# ABL_RP2040.net
KiCad netlist of a schematic drawn in EAGLE
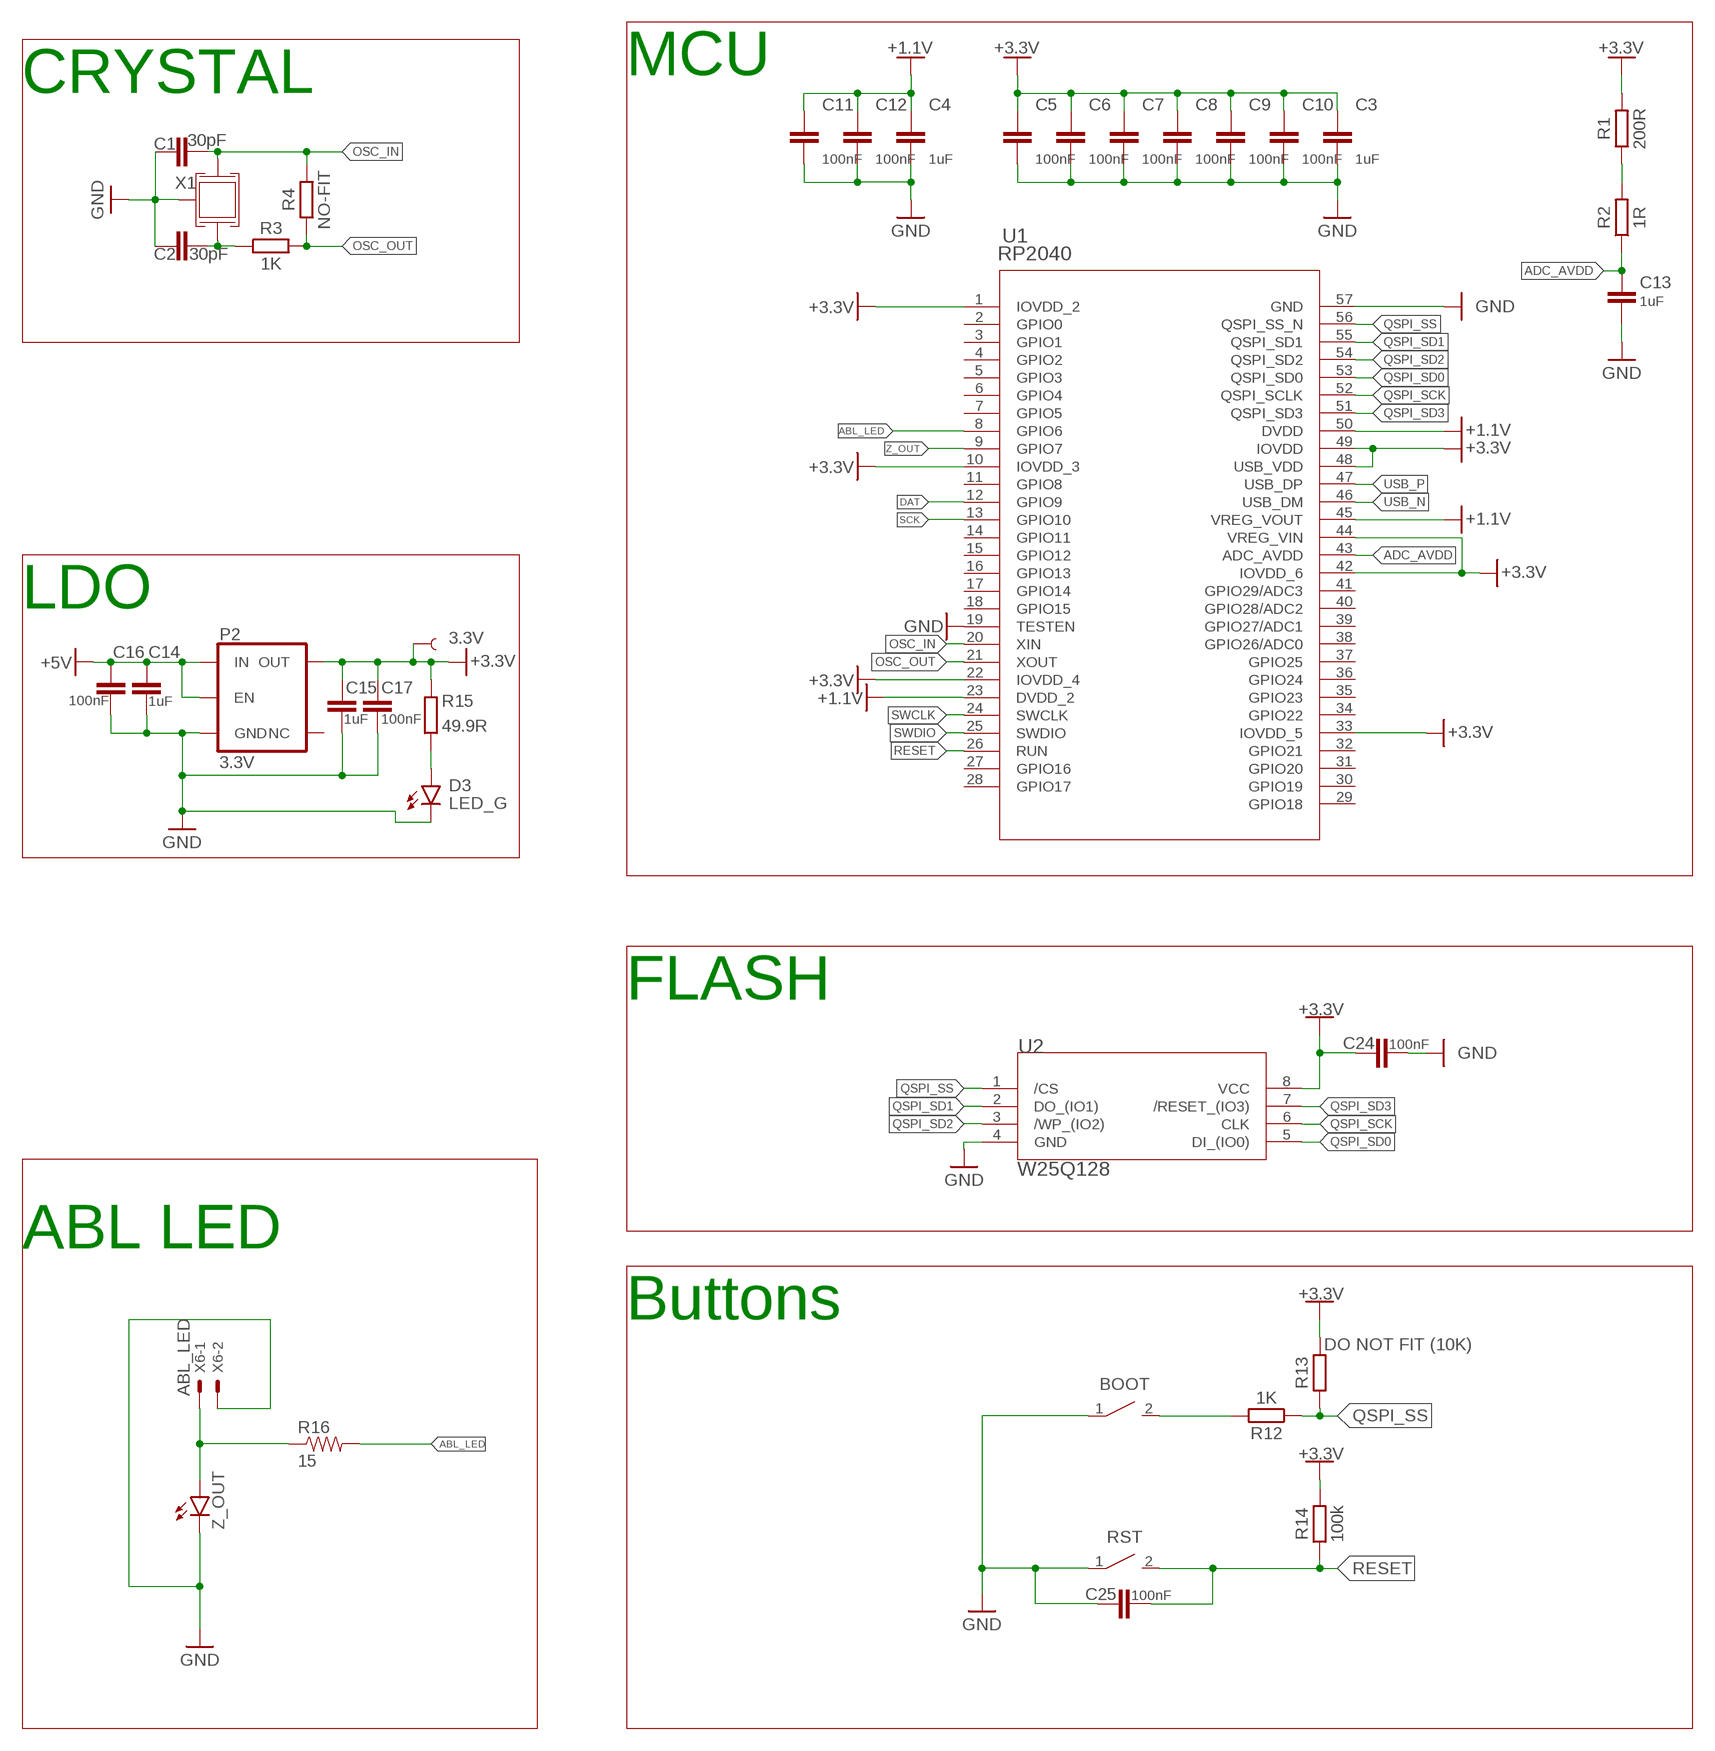
[diagram p0: schematic, sheet 1, part 1 of 2]
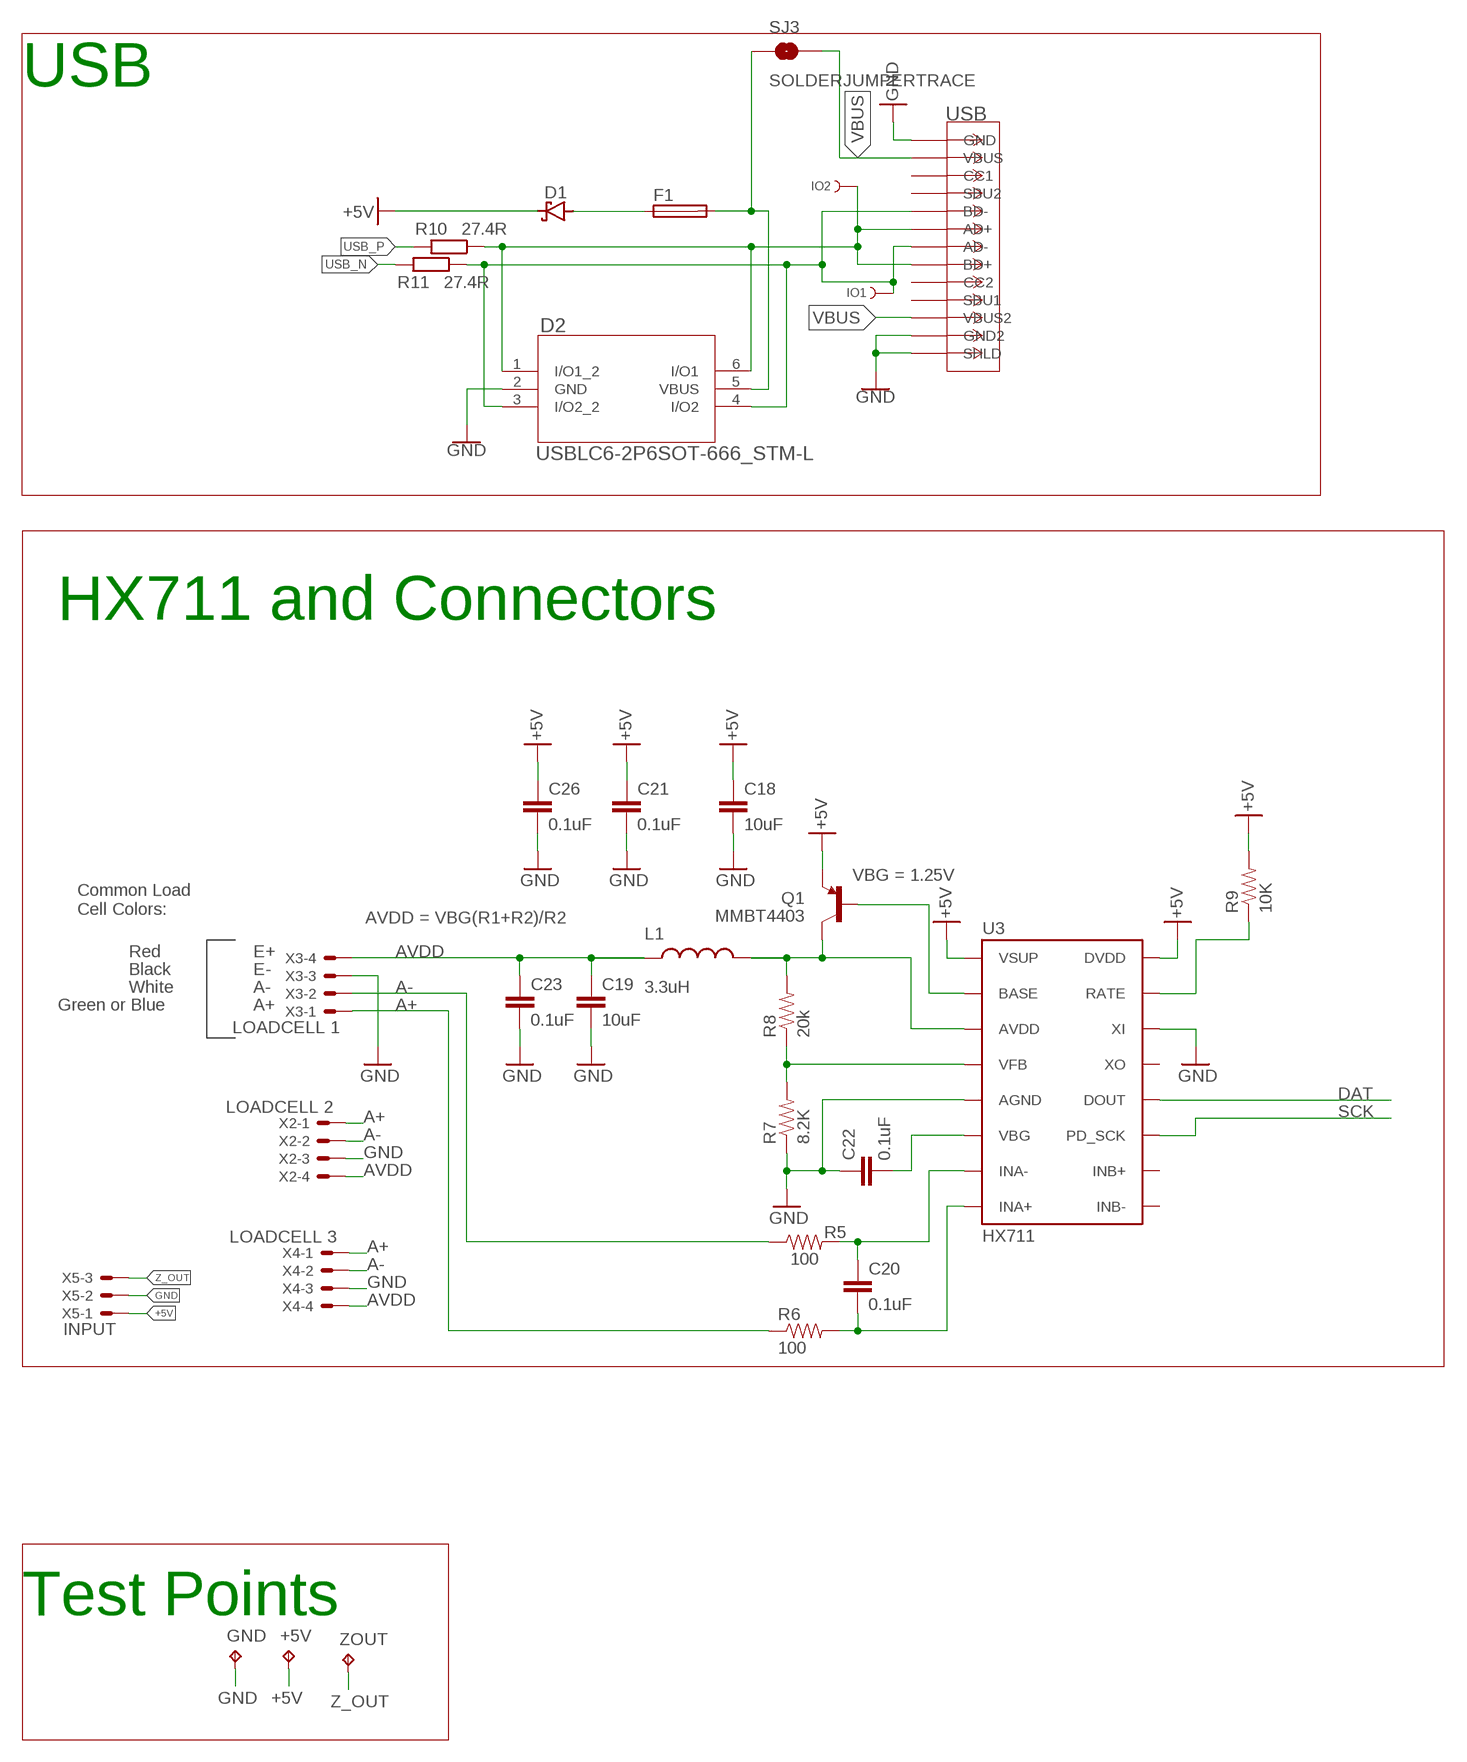
[diagram p1: schematic, sheet 1, part 2 of 2]

(export (version "E")
  (design (tool "Eeschema 10.0.6"))
  (components
    (comp (ref "+5V")
      (value "TPB2,54")
      (footprint "eagle-import:B2,54")
      (libsource (lib "eagle-import") (part "TPB2,54"))
    )
    (comp (ref "3.3V")
      (value "TEST-POINT3X4")
      (footprint "eagle-import:PAD.03X.04")
      (libsource (lib "eagle-import") (part "TEST-POINT3X4"))
    )
    (comp (ref "BOOT")
      (value "B3U-1000P(M)-B")
      (footprint "eagle-import:B3U-1000P(M)-B")
      (fields (field (name "MANUFACTURER") "OMRON"))
      (libsource (lib "eagle-import") (part "B3U-X0001000P(M)-BB3U-1000P(M)-B"))
    )
    (comp (ref "C1")
      (value "30pF")
      (footprint "eagle-import:CAPC1005X60")
      (libsource (lib "eagle-import") (part "CCHIP-0402(1005-METRIC)_"))
    )
    (comp (ref "C2")
      (value "30pF")
      (footprint "eagle-import:CAPC1005X60")
      (libsource (lib "eagle-import") (part "CCHIP-0402(1005-METRIC)_"))
    )
    (comp (ref "C3")
      (value "1uF")
      (footprint "eagle-import:CAPC1005X60")
      (libsource (lib "eagle-import") (part "CCHIP-0402(1005-METRIC)_"))
    )
    (comp (ref "C4")
      (value "1uF")
      (footprint "eagle-import:CAPC1005X60")
      (libsource (lib "eagle-import") (part "CCHIP-0402(1005-METRIC)_"))
    )
    (comp (ref "C5")
      (value "100nF")
      (footprint "eagle-import:CAPC1005X60")
      (libsource (lib "eagle-import") (part "CCHIP-0402(1005-METRIC)_"))
    )
    (comp (ref "C6")
      (value "100nF")
      (footprint "eagle-import:CAPC1005X60")
      (libsource (lib "eagle-import") (part "CCHIP-0402(1005-METRIC)_"))
    )
    (comp (ref "C7")
      (value "100nF")
      (footprint "eagle-import:CAPC1005X60")
      (libsource (lib "eagle-import") (part "CCHIP-0402(1005-METRIC)_"))
    )
    (comp (ref "C8")
      (value "100nF")
      (footprint "eagle-import:CAPC1005X60")
      (libsource (lib "eagle-import") (part "CCHIP-0402(1005-METRIC)_"))
    )
    (comp (ref "C9")
      (value "100nF")
      (footprint "eagle-import:CAPC1005X60")
      (libsource (lib "eagle-import") (part "CCHIP-0402(1005-METRIC)_"))
    )
    (comp (ref "C10")
      (value "100nF")
      (footprint "eagle-import:CAPC1005X60")
      (libsource (lib "eagle-import") (part "CCHIP-0402(1005-METRIC)_"))
    )
    (comp (ref "C11")
      (value "100nF")
      (footprint "eagle-import:CAPC1005X60")
      (libsource (lib "eagle-import") (part "CCHIP-0402(1005-METRIC)_"))
    )
    (comp (ref "C12")
      (value "100nF")
      (footprint "eagle-import:CAPC1005X60")
      (libsource (lib "eagle-import") (part "CCHIP-0402(1005-METRIC)_"))
    )
    (comp (ref "C13")
      (value "1uF")
      (footprint "eagle-import:CAPC1005X60")
      (libsource (lib "eagle-import") (part "CCHIP-0402(1005-METRIC)_"))
    )
    (comp (ref "C14")
      (value "1uF")
      (footprint "eagle-import:CAPC1005X60")
      (libsource (lib "eagle-import") (part "CCHIP-0402(1005-METRIC)_"))
    )
    (comp (ref "C15")
      (value "1uF")
      (footprint "eagle-import:CAPC1005X60")
      (libsource (lib "eagle-import") (part "CCHIP-0402(1005-METRIC)_"))
    )
    (comp (ref "C16")
      (value "100nF")
      (footprint "eagle-import:CAPC1005X60")
      (libsource (lib "eagle-import") (part "CCHIP-0402(1005-METRIC)_"))
    )
    (comp (ref "C17")
      (value "100nF")
      (footprint "eagle-import:CAPC1005X60")
      (libsource (lib "eagle-import") (part "CCHIP-0402(1005-METRIC)_"))
    )
    (comp (ref "C18")
      (value "10uF")
      (footprint "eagle-import:1210")
      (libsource (lib "eagle-import") (part "10UF50V20%(1210)"))
    )
    (comp (ref "C19")
      (value "10uF")
      (footprint "eagle-import:1210")
      (libsource (lib "eagle-import") (part "10UF50V20%(1210)"))
    )
    (comp (ref "C20")
      (value "0.1uF")
      (footprint "eagle-import:0603-CAP")
      (libsource (lib "eagle-import") (part "0.1UF-25V-5%(0603)"))
    )
    (comp (ref "C21")
      (value "0.1uF")
      (footprint "eagle-import:0603-CAP")
      (libsource (lib "eagle-import") (part "0.1UF-25V-5%(0603)"))
    )
    (comp (ref "C22")
      (value "0.1uF")
      (footprint "eagle-import:0603-CAP")
      (libsource (lib "eagle-import") (part "0.1UF-25V-5%(0603)"))
    )
    (comp (ref "C23")
      (value "0.1uF")
      (footprint "eagle-import:0603-CAP")
      (libsource (lib "eagle-import") (part "0.1UF-25V-5%(0603)"))
    )
    (comp (ref "C24")
      (value "100nF")
      (footprint "eagle-import:CAPC1005X60")
      (libsource (lib "eagle-import") (part "CCHIP-0402(1005-METRIC)_"))
    )
    (comp (ref "C25")
      (value "100nF")
      (footprint "eagle-import:CAPC1005X60")
      (libsource (lib "eagle-import") (part "CCHIP-0402(1005-METRIC)_"))
    )
    (comp (ref "C26")
      (value "0.1uF")
      (footprint "eagle-import:0603-CAP")
      (libsource (lib "eagle-import") (part "0.1UF-25V-5%(0603)"))
    )
    (comp (ref "D1")
      (value "MBR0520LT1G")
      (footprint "eagle-import:SODFL3718X115")
      (fields (field (name "MANUFACTURER") "ON Semiconductor"))
      (libsource (lib "eagle-import") (part "SCHOTTKY_DO-219MBR0520LT1G"))
    )
    (comp (ref "D2")
      (value "USBLC6-2P6SOT-666_STM-L")
      (footprint "eagle-import:SOT-666_STM-L")
      (fields
        (field (name "MANUFACTURER_PART_NUMBER") "USBLC6-2P6")
        (field (name "COPYRIGHT") "Copyright (C) 2023 Ultra Librarian. All rights reserved.")
      )
      (libsource (lib "eagle-import") (part "USBLC6-2P6SOT-666_STM-L"))
    )
    (comp (ref "D3")
      (value "LED_G")
      (footprint "eagle-import:LEDC1608X35N_FLAT-G")
      (libsource (lib "eagle-import") (part "CHIP-FLAT-G_0603-0.35MM"))
    )
    (comp (ref "F1")
      (value "FUSE_CHIP-0603(1608-METRIC)")
      (footprint "eagle-import:FUSC1608X60N")
      (libsource (lib "eagle-import") (part "FUSECHIP-0603(1608-METRIC)_"))
    )
    (comp (ref "GND")
      (value "TPB2,54")
      (footprint "eagle-import:B2,54")
      (libsource (lib "eagle-import") (part "TPB2,54"))
    )
    (comp (ref "IO1")
      (value "TEST-POINT3")
      (footprint "eagle-import:PAD.03X.03")
      (libsource (lib "eagle-import") (part "TEST-POINT3"))
    )
    (comp (ref "IO2")
      (value "TEST-POINT3")
      (footprint "eagle-import:PAD.03X.03")
      (libsource (lib "eagle-import") (part "TEST-POINT3"))
    )
    (comp (ref "L1")
      (value "3.3uH")
      (footprint "eagle-import:0805")
      (libsource (lib "eagle-import") (part "INDUCTOR0805-IND"))
    )
    (comp (ref "P2")
      (value "3.3V")
      (footprint "eagle-import:SOT23-5")
      (libsource (lib "eagle-import") (part "V_REG_AP2112K-3.3V"))
    )
    (comp (ref "Q1")
      (value "MMBT4403")
      (footprint "eagle-import:SOT23-3")
      (libsource (lib "eagle-import") (part "TRANSISTOR_PNPMMBT4403"))
    )
    (comp (ref "R1")
      (value "200R")
      (footprint "eagle-import:RESC1005X40")
      (libsource (lib "eagle-import") (part "RCHIP-0402(1005-METRIC)_"))
    )
    (comp (ref "R2")
      (value "1R")
      (footprint "eagle-import:RESC1005X40")
      (libsource (lib "eagle-import") (part "RCHIP-0402(1005-METRIC)_"))
    )
    (comp (ref "R3")
      (value "1K")
      (footprint "eagle-import:RESC1005X40")
      (libsource (lib "eagle-import") (part "RCHIP-0402(1005-METRIC)_"))
    )
    (comp (ref "R4")
      (value "NO-FIT")
      (footprint "eagle-import:RESC1005X40")
      (libsource (lib "eagle-import") (part "RCHIP-0402(1005-METRIC)_"))
    )
    (comp (ref "R5")
      (value "100")
      (footprint "eagle-import:0603-RES@1")
      (libsource (lib "eagle-import") (part "100OHM-1/10W-1%(0603)"))
    )
    (comp (ref "R6")
      (value "100")
      (footprint "eagle-import:0603-RES@1")
      (libsource (lib "eagle-import") (part "100OHM-1/10W-1%(0603)"))
    )
    (comp (ref "R7")
      (value "8.2K")
      (footprint "eagle-import:0603-RES")
      (libsource (lib "eagle-import") (part "8.2KOHM-1/10W-5%(0603)"))
    )
    (comp (ref "R8")
      (value "20k")
      (footprint "eagle-import:0603-RES")
      (libsource (lib "eagle-import") (part "20KOHM1/10W1%(0603)"))
    )
    (comp (ref "R9")
      (value "10K")
      (footprint "eagle-import:0603-RES@1")
      (libsource (lib "eagle-import") (part "10KOHM-1/10W-1%(0603)0603"))
    )
    (comp (ref "R10")
      (value "27.4R")
      (footprint "eagle-import:RESC1005X40")
      (libsource (lib "eagle-import") (part "RCHIP-0402(1005-METRIC)_"))
    )
    (comp (ref "R11")
      (value "27.4R")
      (footprint "eagle-import:RESC1005X40")
      (libsource (lib "eagle-import") (part "RCHIP-0402(1005-METRIC)_"))
    )
    (comp (ref "R12")
      (value "1K")
      (footprint "eagle-import:RESC1005X40")
      (libsource (lib "eagle-import") (part "RCHIP-0402(1005-METRIC)_"))
    )
    (comp (ref "R13")
      (value "DO NOT FIT (10K)")
      (footprint "eagle-import:RESC1005X40")
      (libsource (lib "eagle-import") (part "RCHIP-0402(1005-METRIC)_"))
    )
    (comp (ref "R14")
      (value "100k")
      (footprint "eagle-import:RESC1005X40")
      (libsource (lib "eagle-import") (part "RCHIP-0402(1005-METRIC)_"))
    )
    (comp (ref "R15")
      (value "49.9R")
      (footprint "eagle-import:RESC1005X40")
      (libsource (lib "eagle-import") (part "RCHIP-0402(1005-METRIC)_"))
    )
    (comp (ref "R16")
      (value "15")
      (footprint "eagle-import:0603-RES")
      (libsource (lib "eagle-import") (part "RESISTOR0603"))
    )
    (comp (ref "RST")
      (value "B3U-1000P(M)-B")
      (footprint "eagle-import:B3U-1000P(M)-B")
      (fields (field (name "MANUFACTURER") "OMRON"))
      (libsource (lib "eagle-import") (part "B3U-X0001000P(M)-BB3U-1000P(M)-B"))
    )
    (comp (ref "SJ3")
      (value "SOLDERJUMPERTRACE")
      (footprint "eagle-import:SJ_2S-TRACE")
      (libsource (lib "eagle-import") (part "SOLDERJUMPERTRACE"))
    )
    (comp (ref "U1")
      (value "RP2040")
      (footprint "eagle-import:IC57_RP2040-L")
      (fields (field (name "COPYRIGHT") "Copyright (C) 2023 Ultra Librarian. All rights reserved."))
      (libsource (lib "eagle-import") (part "RP2040IC57_RP2040-L"))
    )
    (comp (ref "U2")
      (value "W25Q128")
      (footprint "eagle-import:SOIC_128JVSIQ_WIN-L")
      (fields
        (field (name "MANUFACTURER_PART_NUMBER") "W25Q128JVSIQ")
        (field (name "COPYRIGHT") "Copyright (C) 2023 Ultra Librarian. All rights reserved.")
      )
      (libsource (lib "eagle-import") (part "W25Q128JVSIQSOIC_128JVSIQ_WIN-L"))
    )
    (comp (ref "U3")
      (value "HX711")
      (footprint "eagle-import:SO16")
      (libsource (lib "eagle-import") (part "HX711HX711"))
    )
    (comp (ref "USB")
      (value "USB-C(KH-TYPE-C-16P)")
      (footprint "eagle-import:CONN12_KH-TYPE-C-16P")
      (fields
        (field (name "MANUFACTURER_PART_NUMBER") "DX07S016JA1R1500")
        (field (name "VENDOR") "LCSC")
        (field (name "COPYRIGHT") "Copyright (C) 2018 Accelerated Designs. All rights reserved")
        (field (name "SOURCELIBRARY") "JAE_Electronics_2020-03-30")
      )
      (libsource (lib "eagle-import") (part "USB-C(KH-TYPE-C-16P)"))
    )
    (comp (ref "X1")
      (value "CRYSTAL_TAXM12M4RLBDDT2T_3225")
      (footprint "eagle-import:CRYSTAL_3225")
      (libsource (lib "eagle-import") (part "CRYSTAL_TAXM12M4RLBDDT2T_3225"))
    )
    (comp (ref "X2")
      (value "LOADCELL 2")
      (footprint "eagle-import:JST-XH-04-PACKAGE-LONG-PAD")
      (libsource (lib "eagle-import") (part "JST-XH-04-PIN-LONG-PAD"))
    )
    (comp (ref "X3")
      (value "LOADCELL 1")
      (footprint "eagle-import:JST-XH-04-PACKAGE-LONG-PAD")
      (libsource (lib "eagle-import") (part "JST-XH-04-PIN-LONG-PAD"))
    )
    (comp (ref "X4")
      (value "LOADCELL 3")
      (footprint "eagle-import:JST-XH-04-PACKAGE-LONG-PAD")
      (libsource (lib "eagle-import") (part "JST-XH-04-PIN-LONG-PAD"))
    )
    (comp (ref "X5")
      (value "INPUT")
      (footprint "eagle-import:JST-XH-03-PACKAGE-LONG-PAD")
      (libsource (lib "eagle-import") (part "JST-XH-03-PIN-LONG-PAD"))
    )
    (comp (ref "X6")
      (value "ABL_LED")
      (footprint "eagle-import:JST-XH-02-PACKAGE-LONG-PAD")
      (libsource (lib "eagle-import") (part "JST-XH-02-PIN-LONG-PAD"))
    )
    (comp (ref "ZOUT")
      (value "TPB2,54")
      (footprint "eagle-import:B2,54")
      (libsource (lib "eagle-import") (part "TPB2,54"))
    )
    (comp (ref "Z_OUT")
      (value "LEDSML0603")
      (footprint "eagle-import:SML0603")
      (libsource (lib "eagle-import") (part "LEDSML0603"))
    )
  )
  (nets
    (net (code "1") (name "+1.1V") (class "Default")
      (node (ref "C11") (pin "1") (pinfunction "1_1") (pintype "passive"))
      (node (ref "C12") (pin "1") (pinfunction "1_1") (pintype "passive"))
      (node (ref "C4") (pin "1") (pinfunction "1_1") (pintype "passive"))
      (node (ref "U1") (pin "23") (pinfunction "DVDD_2_23") (pintype "power_in"))
      (node (ref "U1") (pin "45") (pinfunction "VREG_VOUT_45") (pintype "output"))
      (node (ref "U1") (pin "50") (pinfunction "DVDD_50") (pintype "power_in"))
    )
    (net (code "2") (name "+3.3V") (class "Default")
      (node (ref "3.3V") (pin "P$1") (pinfunction "1_P$1") (pintype "bidirectional"))
      (node (ref "C10") (pin "1") (pinfunction "1_1") (pintype "passive"))
      (node (ref "C15") (pin "1") (pinfunction "1_1") (pintype "passive"))
      (node (ref "C17") (pin "1") (pinfunction "1_1") (pintype "passive"))
      (node (ref "C24") (pin "1") (pinfunction "1_1") (pintype "passive"))
      (node (ref "C3") (pin "1") (pinfunction "1_1") (pintype "passive"))
      (node (ref "C5") (pin "1") (pinfunction "1_1") (pintype "passive"))
      (node (ref "C6") (pin "1") (pinfunction "1_1") (pintype "passive"))
      (node (ref "C7") (pin "1") (pinfunction "1_1") (pintype "passive"))
      (node (ref "C8") (pin "1") (pinfunction "1_1") (pintype "passive"))
      (node (ref "C9") (pin "1") (pinfunction "1_1") (pintype "passive"))
      (node (ref "P2") (pin "5") (pinfunction "OUT_5") (pintype "passive"))
      (node (ref "R1") (pin "2") (pinfunction "2_2") (pintype "passive"))
      (node (ref "R13") (pin "2") (pinfunction "2_2") (pintype "passive"))
      (node (ref "R14") (pin "2") (pinfunction "2_2") (pintype "passive"))
      (node (ref "R15") (pin "2") (pinfunction "2_2") (pintype "passive"))
      (node (ref "U1") (pin "1") (pinfunction "IOVDD_2_1") (pintype "power_in"))
      (node (ref "U1") (pin "10") (pinfunction "IOVDD_3_10") (pintype "power_in"))
      (node (ref "U1") (pin "22") (pinfunction "IOVDD_4_22") (pintype "power_in"))
      (node (ref "U1") (pin "33") (pinfunction "IOVDD_5_33") (pintype "power_in"))
      (node (ref "U1") (pin "42") (pinfunction "IOVDD_6_42") (pintype "power_in"))
      (node (ref "U1") (pin "44") (pinfunction "VREG_VIN_44") (pintype "passive"))
      (node (ref "U1") (pin "48") (pinfunction "USB_VDD_48") (pintype "power_in"))
      (node (ref "U1") (pin "49") (pinfunction "IOVDD_49") (pintype "power_in"))
      (node (ref "U2") (pin "8") (pinfunction "VCC_8") (pintype "power_in"))
    )
    (net (code "3") (name "+5V") (class "Default")
      (node (ref "+5V") (pin "TP") (pinfunction "TP_TP") (pintype "input"))
      (node (ref "C14") (pin "1") (pinfunction "1_1") (pintype "passive"))
      (node (ref "C16") (pin "1") (pinfunction "1_1") (pintype "passive"))
      (node (ref "C18") (pin "1") (pinfunction "1_1") (pintype "passive"))
      (node (ref "C21") (pin "1") (pinfunction "1_1") (pintype "passive"))
      (node (ref "C26") (pin "1") (pinfunction "1_1") (pintype "passive"))
      (node (ref "D1") (pin "1") (pinfunction "C_1") (pintype "passive"))
      (node (ref "P2") (pin "1") (pinfunction "IN_1") (pintype "input"))
      (node (ref "P2") (pin "3") (pinfunction "EN_3") (pintype "input"))
      (node (ref "Q1") (pin "2") (pinfunction "E_2") (pintype "passive"))
      (node (ref "R9") (pin "2") (pinfunction "2_2") (pintype "passive"))
      (node (ref "U3") (pin "1") (pinfunction "VSUP_1") (pintype "bidirectional"))
      (node (ref "U3") (pin "16") (pinfunction "DVDD_16") (pintype "bidirectional"))
      (node (ref "X5") (pin "1") (pinfunction "S_1") (pintype "passive"))
    )
    (net (code "4") (name "/A+") (class "Default")
      (node (ref "R6") (pin "1") (pinfunction "1_1") (pintype "passive"))
      (node (ref "X2") (pin "1") (pinfunction "S_1") (pintype "passive"))
      (node (ref "X3") (pin "1") (pinfunction "S_1") (pintype "passive"))
      (node (ref "X4") (pin "1") (pinfunction "S_1") (pintype "passive"))
    )
    (net (code "5") (name "/A-") (class "Default")
      (node (ref "R5") (pin "1") (pinfunction "1_1") (pintype "passive"))
      (node (ref "X2") (pin "2") (pinfunction "S_2") (pintype "passive"))
      (node (ref "X3") (pin "2") (pinfunction "S_2") (pintype "passive"))
      (node (ref "X4") (pin "2") (pinfunction "S_2") (pintype "passive"))
    )
    (net (code "6") (name "/AVDD") (class "Default")
      (node (ref "C19") (pin "1") (pinfunction "1_1") (pintype "passive"))
      (node (ref "C23") (pin "1") (pinfunction "1_1") (pintype "passive"))
      (node (ref "L1") (pin "1") (pinfunction "1_1") (pintype "passive"))
      (node (ref "X2") (pin "4") (pinfunction "S_4") (pintype "passive"))
      (node (ref "X3") (pin "4") (pinfunction "S_4") (pintype "passive"))
      (node (ref "X4") (pin "4") (pinfunction "S_4") (pintype "passive"))
    )
    (net (code "7") (name "ABL_LED") (class "Default")
      (node (ref "R16") (pin "2") (pinfunction "2_2") (pintype "passive"))
      (node (ref "U1") (pin "8") (pinfunction "GPIO6_8") (pintype "bidirectional"))
    )
    (net (code "8") (name "ADC_AVDD") (class "Default")
      (node (ref "C13") (pin "1") (pinfunction "1_1") (pintype "passive"))
      (node (ref "R2") (pin "1") (pinfunction "1_1") (pintype "passive"))
      (node (ref "U1") (pin "43") (pinfunction "ADC_AVDD_43") (pintype "power_in"))
    )
    (net (code "9") (name "DAT") (class "Default")
      (node (ref "U1") (pin "12") (pinfunction "GPIO9_12") (pintype "bidirectional"))
      (node (ref "U3") (pin "12") (pinfunction "DOUT_12") (pintype "bidirectional"))
    )
    (net (code "10") (name "GND") (class "Default")
      (node (ref "BOOT") (pin "1") (pinfunction "1_1") (pintype "bidirectional"))
      (node (ref "C1") (pin "2") (pinfunction "2_2") (pintype "passive"))
      (node (ref "C10") (pin "2") (pinfunction "2_2") (pintype "passive"))
      (node (ref "C11") (pin "2") (pinfunction "2_2") (pintype "passive"))
      (node (ref "C12") (pin "2") (pinfunction "2_2") (pintype "passive"))
      (node (ref "C13") (pin "2") (pinfunction "2_2") (pintype "passive"))
      (node (ref "C14") (pin "2") (pinfunction "2_2") (pintype "passive"))
      (node (ref "C15") (pin "2") (pinfunction "2_2") (pintype "passive"))
      (node (ref "C16") (pin "2") (pinfunction "2_2") (pintype "passive"))
      (node (ref "C17") (pin "2") (pinfunction "2_2") (pintype "passive"))
      (node (ref "C18") (pin "2") (pinfunction "2_2") (pintype "passive"))
      (node (ref "C19") (pin "2") (pinfunction "2_2") (pintype "passive"))
      (node (ref "C2") (pin "1") (pinfunction "1_1") (pintype "passive"))
      (node (ref "C21") (pin "2") (pinfunction "2_2") (pintype "passive"))
      (node (ref "C22") (pin "1") (pinfunction "1_1") (pintype "passive"))
      (node (ref "C23") (pin "2") (pinfunction "2_2") (pintype "passive"))
      (node (ref "C24") (pin "2") (pinfunction "2_2") (pintype "passive"))
      (node (ref "C25") (pin "1") (pinfunction "1_1") (pintype "passive"))
      (node (ref "C26") (pin "2") (pinfunction "2_2") (pintype "passive"))
      (node (ref "C3") (pin "2") (pinfunction "2_2") (pintype "passive"))
      (node (ref "C4") (pin "2") (pinfunction "2_2") (pintype "passive"))
      (node (ref "C5") (pin "2") (pinfunction "2_2") (pintype "passive"))
      (node (ref "C6") (pin "2") (pinfunction "2_2") (pintype "passive"))
      (node (ref "C7") (pin "2") (pinfunction "2_2") (pintype "passive"))
      (node (ref "C8") (pin "2") (pinfunction "2_2") (pintype "passive"))
      (node (ref "C9") (pin "2") (pinfunction "2_2") (pintype "passive"))
      (node (ref "D2") (pin "2") (pinfunction "GND_2") (pintype "power_in"))
      (node (ref "D3") (pin "C") (pinfunction "C_C") (pintype "passive"))
      (node (ref "GND") (pin "TP") (pinfunction "TP_TP") (pintype "input"))
      (node (ref "P2") (pin "2") (pinfunction "GND_2") (pintype "input"))
      (node (ref "R7") (pin "1") (pinfunction "1_1") (pintype "passive"))
      (node (ref "RST") (pin "1") (pinfunction "1_1") (pintype "bidirectional"))
      (node (ref "U1") (pin "19") (pinfunction "TESTEN_19") (pintype "passive"))
      (node (ref "U1") (pin "57") (pinfunction "GND_57") (pintype "passive"))
      (node (ref "U2") (pin "4") (pinfunction "GND_4") (pintype "passive"))
      (node (ref "U3") (pin "14") (pinfunction "XI_14") (pintype "bidirectional"))
      (node (ref "U3") (pin "5") (pinfunction "AGND_5") (pintype "bidirectional"))
      (node (ref "USB") (pin "1") (pinfunction "GND_1") (pintype "power_in"))
      (node (ref "USB") (pin "12") (pinfunction "GND2_12") (pintype "power_in"))
      (node (ref "USB") (pin "13") (pinfunction "SHLD_13") (pintype "passive"))
      (node (ref "USB") (pin "14") (pinfunction "SHLD_14") (pintype "passive"))
      (node (ref "USB") (pin "15") (pinfunction "SHLD_15") (pintype "passive"))
      (node (ref "USB") (pin "16") (pinfunction "SHLD_16") (pintype "passive"))
      (node (ref "USB") (pin "18") (pinfunction "SHLD_18") (pintype "passive"))
      (node (ref "USB") (pin "19") (pinfunction "SHLD_19") (pintype "passive"))
      (node (ref "USB") (pin "20") (pinfunction "SHLD_20") (pintype "passive"))
      (node (ref "USB") (pin "21") (pinfunction "SHLD_21") (pintype "passive"))
      (node (ref "USB") (pin "24") (pinfunction "SHLD_24") (pintype "passive"))
      (node (ref "USB") (pin "25") (pinfunction "SHLD_25") (pintype "passive"))
      (node (ref "USB") (pin "26") (pinfunction "SHLD_26") (pintype "passive"))
      (node (ref "USB") (pin "27") (pinfunction "SHLD_27") (pintype "passive"))
      (node (ref "USB") (pin "28") (pinfunction "SHLD_28") (pintype "passive"))
      (node (ref "USB") (pin "29") (pinfunction "SHLD_29") (pintype "passive"))
      (node (ref "USB") (pin "37") (pinfunction "SHLD_37") (pintype "passive"))
      (node (ref "USB") (pin "39") (pinfunction "SHLD_39") (pintype "passive"))
      (node (ref "USB") (pin "41") (pinfunction "SHLD_41") (pintype "passive"))
      (node (ref "USB") (pin "43") (pinfunction "SHLD_43") (pintype "passive"))
      (node (ref "X1") (pin "P$2") (pinfunction "GND_P$2") (pintype "bidirectional"))
      (node (ref "X1") (pin "P$4") (pinfunction "GND_P$4") (pintype "bidirectional"))
      (node (ref "X2") (pin "3") (pinfunction "S_3") (pintype "passive"))
      (node (ref "X3") (pin "3") (pinfunction "S_3") (pintype "passive"))
      (node (ref "X4") (pin "3") (pinfunction "S_3") (pintype "passive"))
      (node (ref "X5") (pin "2") (pinfunction "S_2") (pintype "passive"))
      (node (ref "X6") (pin "2") (pinfunction "S_2") (pintype "passive"))
      (node (ref "Z_OUT") (pin "C") (pinfunction "C_C") (pintype "passive"))
    )
    (net (code "11") (name "Net-(BOOT-Pad2)") (class "Default")
      (node (ref "BOOT") (pin "2") (pinfunction "2_2") (pintype "bidirectional"))
      (node (ref "R12") (pin "2") (pinfunction "2_2") (pintype "passive"))
    )
    (net (code "12") (name "Net-(D1-A)") (class "Default")
      (node (ref "D1") (pin "2") (pinfunction "A_2") (pintype "passive"))
      (node (ref "F1") (pin "1") (pinfunction "1_1") (pintype "passive"))
    )
    (net (code "13") (name "Net-(D2-I{slash}O1)") (class "Default")
      (node (ref "D2") (pin "1") (pinfunction "I/O1_2_1") (pintype "bidirectional"))
      (node (ref "D2") (pin "6") (pinfunction "I/O1_6") (pintype "bidirectional"))
      (node (ref "IO2") (pin "P$1") (pinfunction "1_P$1") (pintype "bidirectional"))
      (node (ref "R10") (pin "1") (pinfunction "1_1") (pintype "passive"))
      (node (ref "USB") (pin "6") (pinfunction "AD+_6") (pintype "passive"))
      (node (ref "USB") (pin "8") (pinfunction "BD+_8") (pintype "passive"))
    )
    (net (code "14") (name "Net-(D2-I{slash}O2)") (class "Default")
      (node (ref "D2") (pin "3") (pinfunction "I/O2_2_3") (pintype "bidirectional"))
      (node (ref "D2") (pin "4") (pinfunction "I/O2_4") (pintype "bidirectional"))
      (node (ref "IO1") (pin "P$1") (pinfunction "1_P$1") (pintype "bidirectional"))
      (node (ref "R11") (pin "1") (pinfunction "1_1") (pintype "passive"))
      (node (ref "USB") (pin "5") (pinfunction "BD-_5") (pintype "passive"))
      (node (ref "USB") (pin "7") (pinfunction "AD-_7") (pintype "passive"))
    )
    (net (code "15") (name "Net-(D2-VBUS)") (class "Default")
      (node (ref "D2") (pin "5") (pinfunction "VBUS_5") (pintype "power_in"))
      (node (ref "F1") (pin "2") (pinfunction "2_2") (pintype "passive"))
      (node (ref "SJ3") (pin "1") (pinfunction "1_1") (pintype "passive"))
    )
    (net (code "16") (name "Net-(D3-PadA)") (class "Default")
      (node (ref "D3") (pin "A") (pinfunction "A_A") (pintype "passive"))
      (node (ref "R15") (pin "1") (pinfunction "1_1") (pintype "passive"))
    )
    (net (code "17") (name "Net-(Q1-B)") (class "Default")
      (node (ref "Q1") (pin "1") (pinfunction "B_1") (pintype "passive"))
      (node (ref "U3") (pin "2") (pinfunction "BASE_2") (pintype "bidirectional"))
    )
    (net (code "18") (name "Net-(Q1-C)") (class "Default")
      (node (ref "L1") (pin "2") (pinfunction "2_2") (pintype "passive"))
      (node (ref "Q1") (pin "3") (pinfunction "C_3") (pintype "passive"))
      (node (ref "R8") (pin "2") (pinfunction "2_2") (pintype "passive"))
      (node (ref "U3") (pin "3") (pinfunction "AVDD_3") (pintype "bidirectional"))
    )
    (net (code "19") (name "Net-(R1-Pad1)") (class "Default")
      (node (ref "R1") (pin "1") (pinfunction "1_1") (pintype "passive"))
      (node (ref "R2") (pin "2") (pinfunction "2_2") (pintype "passive"))
    )
    (net (code "20") (name "Net-(U3-INA+)") (class "Default")
      (node (ref "C20") (pin "2") (pinfunction "2_2") (pintype "passive"))
      (node (ref "R6") (pin "2") (pinfunction "2_2") (pintype "passive"))
      (node (ref "U3") (pin "8") (pinfunction "INA+_8") (pintype "bidirectional"))
    )
    (net (code "21") (name "Net-(U3-INA-)") (class "Default")
      (node (ref "C20") (pin "1") (pinfunction "1_1") (pintype "passive"))
      (node (ref "R5") (pin "2") (pinfunction "2_2") (pintype "passive"))
      (node (ref "U3") (pin "7") (pinfunction "INA-_7") (pintype "bidirectional"))
    )
    (net (code "22") (name "Net-(U3-RATE)") (class "Default")
      (node (ref "R9") (pin "1") (pinfunction "1_1") (pintype "passive"))
      (node (ref "U3") (pin "15") (pinfunction "RATE_15") (pintype "bidirectional"))
    )
    (net (code "23") (name "Net-(U3-VBG)") (class "Default")
      (node (ref "C22") (pin "2") (pinfunction "2_2") (pintype "passive"))
      (node (ref "U3") (pin "6") (pinfunction "VBG_6") (pintype "bidirectional"))
    )
    (net (code "24") (name "Net-(U3-VFB)") (class "Default")
      (node (ref "R7") (pin "2") (pinfunction "2_2") (pintype "passive"))
      (node (ref "R8") (pin "1") (pinfunction "1_1") (pintype "passive"))
      (node (ref "U3") (pin "4") (pinfunction "VFB_4") (pintype "bidirectional"))
    )
    (net (code "25") (name "Net-(X1-P2)") (class "Default")
      (node (ref "C2") (pin "2") (pinfunction "2_2") (pintype "passive"))
      (node (ref "R3") (pin "1") (pinfunction "1_1") (pintype "passive"))
      (node (ref "X1") (pin "P$3") (pinfunction "P2_P$3") (pintype "bidirectional"))
    )
    (net (code "26") (name "Net-(X6A-S)") (class "Default")
      (node (ref "R16") (pin "1") (pinfunction "1_1") (pintype "passive"))
      (node (ref "X6") (pin "1") (pinfunction "S_1") (pintype "passive"))
      (node (ref "Z_OUT") (pin "A") (pinfunction "A_A") (pintype "passive"))
    )
    (net (code "27") (name "OSC_IN") (class "Default")
      (node (ref "C1") (pin "1") (pinfunction "1_1") (pintype "passive"))
      (node (ref "R4") (pin "2") (pinfunction "2_2") (pintype "passive"))
      (node (ref "U1") (pin "20") (pinfunction "XIN_20") (pintype "passive"))
      (node (ref "X1") (pin "P$1") (pinfunction "P1_P$1") (pintype "bidirectional"))
    )
    (net (code "28") (name "OSC_OUT") (class "Default")
      (node (ref "R3") (pin "2") (pinfunction "2_2") (pintype "passive"))
      (node (ref "R4") (pin "1") (pinfunction "1_1") (pintype "passive"))
      (node (ref "U1") (pin "21") (pinfunction "XOUT_21") (pintype "output"))
    )
    (net (code "29") (name "QSPI_SCK") (class "Default")
      (node (ref "U1") (pin "52") (pinfunction "QSPI_SCLK_52") (pintype "passive"))
      (node (ref "U2") (pin "6") (pinfunction "CLK_6") (pintype "passive"))
    )
    (net (code "30") (name "QSPI_SD0") (class "Default")
      (node (ref "U1") (pin "53") (pinfunction "QSPI_SD0_53") (pintype "bidirectional"))
      (node (ref "U2") (pin "5") (pinfunction "DI_(IO0)_5") (pintype "passive"))
    )
    (net (code "31") (name "QSPI_SD1") (class "Default")
      (node (ref "U1") (pin "55") (pinfunction "QSPI_SD1_55") (pintype "bidirectional"))
      (node (ref "U2") (pin "2") (pinfunction "DO_(IO1)_2") (pintype "passive"))
    )
    (net (code "32") (name "QSPI_SD2") (class "Default")
      (node (ref "U1") (pin "54") (pinfunction "QSPI_SD2_54") (pintype "bidirectional"))
      (node (ref "U2") (pin "3") (pinfunction "/WP_(IO2)_3") (pintype "passive"))
    )
    (net (code "33") (name "QSPI_SD3") (class "Default")
      (node (ref "U1") (pin "51") (pinfunction "QSPI_SD3_51") (pintype "bidirectional"))
      (node (ref "U2") (pin "7") (pinfunction "/RESET_(IO3)_7") (pintype "passive"))
    )
    (net (code "34") (name "QSPI_SS") (class "Default")
      (node (ref "R12") (pin "1") (pinfunction "1_1") (pintype "passive"))
      (node (ref "R13") (pin "1") (pinfunction "1_1") (pintype "passive"))
      (node (ref "U1") (pin "56") (pinfunction "QSPI_SS_N_56") (pintype "passive"))
      (node (ref "U2") (pin "1") (pinfunction "/CS_1") (pintype "passive"))
    )
    (net (code "35") (name "RESET") (class "Default")
      (node (ref "C25") (pin "2") (pinfunction "2_2") (pintype "passive"))
      (node (ref "R14") (pin "1") (pinfunction "1_1") (pintype "passive"))
      (node (ref "RST") (pin "2") (pinfunction "2_2") (pintype "bidirectional"))
      (node (ref "U1") (pin "26") (pinfunction "RUN_26") (pintype "passive"))
    )
    (net (code "36") (name "SCK") (class "Default")
      (node (ref "U1") (pin "13") (pinfunction "GPIO10_13") (pintype "bidirectional"))
      (node (ref "U3") (pin "11") (pinfunction "PD_SCK_11") (pintype "bidirectional"))
    )
    (net (code "37") (name "SWCLK") (class "Default")
      (node (ref "U1") (pin "24") (pinfunction "SWCLK_24") (pintype "passive"))
    )
    (net (code "38") (name "SWDIO") (class "Default")
      (node (ref "U1") (pin "25") (pinfunction "SWDIO_25") (pintype "passive"))
    )
    (net (code "39") (name "USB_N") (class "Default")
      (node (ref "R11") (pin "2") (pinfunction "2_2") (pintype "passive"))
      (node (ref "U1") (pin "46") (pinfunction "USB_DM_46") (pintype "passive"))
    )
    (net (code "40") (name "USB_P") (class "Default")
      (node (ref "R10") (pin "2") (pinfunction "2_2") (pintype "passive"))
      (node (ref "U1") (pin "47") (pinfunction "USB_DP_47") (pintype "passive"))
    )
    (net (code "41") (name "VBUS") (class "Default")
      (node (ref "SJ3") (pin "2") (pinfunction "2_2") (pintype "passive"))
      (node (ref "USB") (pin "11") (pinfunction "VBUS2_11") (pintype "power_in"))
      (node (ref "USB") (pin "2") (pinfunction "VBUS_2") (pintype "power_in"))
    )
    (net (code "42") (name "Z_OUT") (class "Default")
      (node (ref "U1") (pin "9") (pinfunction "GPIO7_9") (pintype "bidirectional"))
      (node (ref "X5") (pin "3") (pinfunction "S_3") (pintype "passive"))
      (node (ref "ZOUT") (pin "TP") (pinfunction "TP_TP") (pintype "input"))
    )
    (net (code "43") (name "unconnected-(P2-NC-Pad4)") (class "Default")
      (node (ref "P2") (pin "4") (pinfunction "NC_4") (pintype "no_connect"))
    )
    (net (code "44") (name "unconnected-(U1-GPIO0-Pad2)") (class "Default")
      (node (ref "U1") (pin "2") (pinfunction "GPIO0_2") (pintype "bidirectional"))
    )
    (net (code "45") (name "unconnected-(U1-GPIO1-Pad3)") (class "Default")
      (node (ref "U1") (pin "3") (pinfunction "GPIO1_3") (pintype "bidirectional"))
    )
    (net (code "46") (name "unconnected-(U1-GPIO2-Pad4)") (class "Default")
      (node (ref "U1") (pin "4") (pinfunction "GPIO2_4") (pintype "bidirectional"))
    )
    (net (code "47") (name "unconnected-(U1-GPIO3-Pad5)") (class "Default")
      (node (ref "U1") (pin "5") (pinfunction "GPIO3_5") (pintype "bidirectional"))
    )
    (net (code "48") (name "unconnected-(U1-GPIO4-Pad6)") (class "Default")
      (node (ref "U1") (pin "6") (pinfunction "GPIO4_6") (pintype "bidirectional"))
    )
    (net (code "49") (name "unconnected-(U1-GPIO5-Pad7)") (class "Default")
      (node (ref "U1") (pin "7") (pinfunction "GPIO5_7") (pintype "bidirectional"))
    )
    (net (code "50") (name "unconnected-(U1-GPIO8-Pad11)") (class "Default")
      (node (ref "U1") (pin "11") (pinfunction "GPIO8_11") (pintype "bidirectional"))
    )
    (net (code "51") (name "unconnected-(U1-GPIO11-Pad14)") (class "Default")
      (node (ref "U1") (pin "14") (pinfunction "GPIO11_14") (pintype "bidirectional"))
    )
    (net (code "52") (name "unconnected-(U1-GPIO12-Pad15)") (class "Default")
      (node (ref "U1") (pin "15") (pinfunction "GPIO12_15") (pintype "bidirectional"))
    )
    (net (code "53") (name "unconnected-(U1-GPIO13-Pad16)") (class "Default")
      (node (ref "U1") (pin "16") (pinfunction "GPIO13_16") (pintype "bidirectional"))
    )
    (net (code "54") (name "unconnected-(U1-GPIO14-Pad17)") (class "Default")
      (node (ref "U1") (pin "17") (pinfunction "GPIO14_17") (pintype "bidirectional"))
    )
    (net (code "55") (name "unconnected-(U1-GPIO15-Pad18)") (class "Default")
      (node (ref "U1") (pin "18") (pinfunction "GPIO15_18") (pintype "bidirectional"))
    )
    (net (code "56") (name "unconnected-(U1-GPIO16-Pad27)") (class "Default")
      (node (ref "U1") (pin "27") (pinfunction "GPIO16_27") (pintype "bidirectional"))
    )
    (net (code "57") (name "unconnected-(U1-GPIO17-Pad28)") (class "Default")
      (node (ref "U1") (pin "28") (pinfunction "GPIO17_28") (pintype "bidirectional"))
    )
    (net (code "58") (name "unconnected-(U1-GPIO18-Pad29)") (class "Default")
      (node (ref "U1") (pin "29") (pinfunction "GPIO18_29") (pintype "bidirectional"))
    )
    (net (code "59") (name "unconnected-(U1-GPIO19-Pad30)") (class "Default")
      (node (ref "U1") (pin "30") (pinfunction "GPIO19_30") (pintype "bidirectional"))
    )
    (net (code "60") (name "unconnected-(U1-GPIO20-Pad31)") (class "Default")
      (node (ref "U1") (pin "31") (pinfunction "GPIO20_31") (pintype "bidirectional"))
    )
    (net (code "61") (name "unconnected-(U1-GPIO21-Pad32)") (class "Default")
      (node (ref "U1") (pin "32") (pinfunction "GPIO21_32") (pintype "bidirectional"))
    )
    (net (code "62") (name "unconnected-(U1-GPIO22-Pad34)") (class "Default")
      (node (ref "U1") (pin "34") (pinfunction "GPIO22_34") (pintype "bidirectional"))
    )
    (net (code "63") (name "unconnected-(U1-GPIO23-Pad35)") (class "Default")
      (node (ref "U1") (pin "35") (pinfunction "GPIO23_35") (pintype "bidirectional"))
    )
    (net (code "64") (name "unconnected-(U1-GPIO24-Pad36)") (class "Default")
      (node (ref "U1") (pin "36") (pinfunction "GPIO24_36") (pintype "bidirectional"))
    )
    (net (code "65") (name "unconnected-(U1-GPIO25-Pad37)") (class "Default")
      (node (ref "U1") (pin "37") (pinfunction "GPIO25_37") (pintype "bidirectional"))
    )
    (net (code "66") (name "unconnected-(U1-GPIO26{slash}ADC0-Pad38)") (class "Default")
      (node (ref "U1") (pin "38") (pinfunction "GPIO26/ADC0_38") (pintype "bidirectional"))
    )
    (net (code "67") (name "unconnected-(U1-GPIO27{slash}ADC1-Pad39)") (class "Default")
      (node (ref "U1") (pin "39") (pinfunction "GPIO27/ADC1_39") (pintype "bidirectional"))
    )
    (net (code "68") (name "unconnected-(U1-GPIO28{slash}ADC2-Pad40)") (class "Default")
      (node (ref "U1") (pin "40") (pinfunction "GPIO28/ADC2_40") (pintype "bidirectional"))
    )
    (net (code "69") (name "unconnected-(U1-GPIO29{slash}ADC3-Pad41)") (class "Default")
      (node (ref "U1") (pin "41") (pinfunction "GPIO29/ADC3_41") (pintype "bidirectional"))
    )
    (net (code "70") (name "unconnected-(U3-INB+-Pad10)") (class "Default")
      (node (ref "U3") (pin "10") (pinfunction "INB+_10") (pintype "bidirectional"))
    )
    (net (code "71") (name "unconnected-(U3-INB--Pad9)") (class "Default")
      (node (ref "U3") (pin "9") (pinfunction "INB-_9") (pintype "bidirectional"))
    )
    (net (code "72") (name "unconnected-(U3-XO-Pad13)") (class "Default")
      (node (ref "U3") (pin "13") (pinfunction "XO_13") (pintype "bidirectional"))
    )
    (net (code "73") (name "unconnected-(USB-CC1-Pad3)") (class "Default")
      (node (ref "USB") (pin "3") (pinfunction "CC1_3") (pintype "passive"))
    )
    (net (code "74") (name "unconnected-(USB-CC2-Pad9)") (class "Default")
      (node (ref "USB") (pin "9") (pinfunction "CC2_9") (pintype "passive"))
    )
    (net (code "75") (name "unconnected-(USB-SBU1-Pad10)") (class "Default")
      (node (ref "USB") (pin "10") (pinfunction "SBU1_10") (pintype "passive"))
    )
    (net (code "76") (name "unconnected-(USB-SBU2-Pad4)") (class "Default")
      (node (ref "USB") (pin "4") (pinfunction "SBU2_4") (pintype "passive"))
    )
  )
)
